# RGMII.net
KiCad netlist of a schematic drawn in Altium Designer
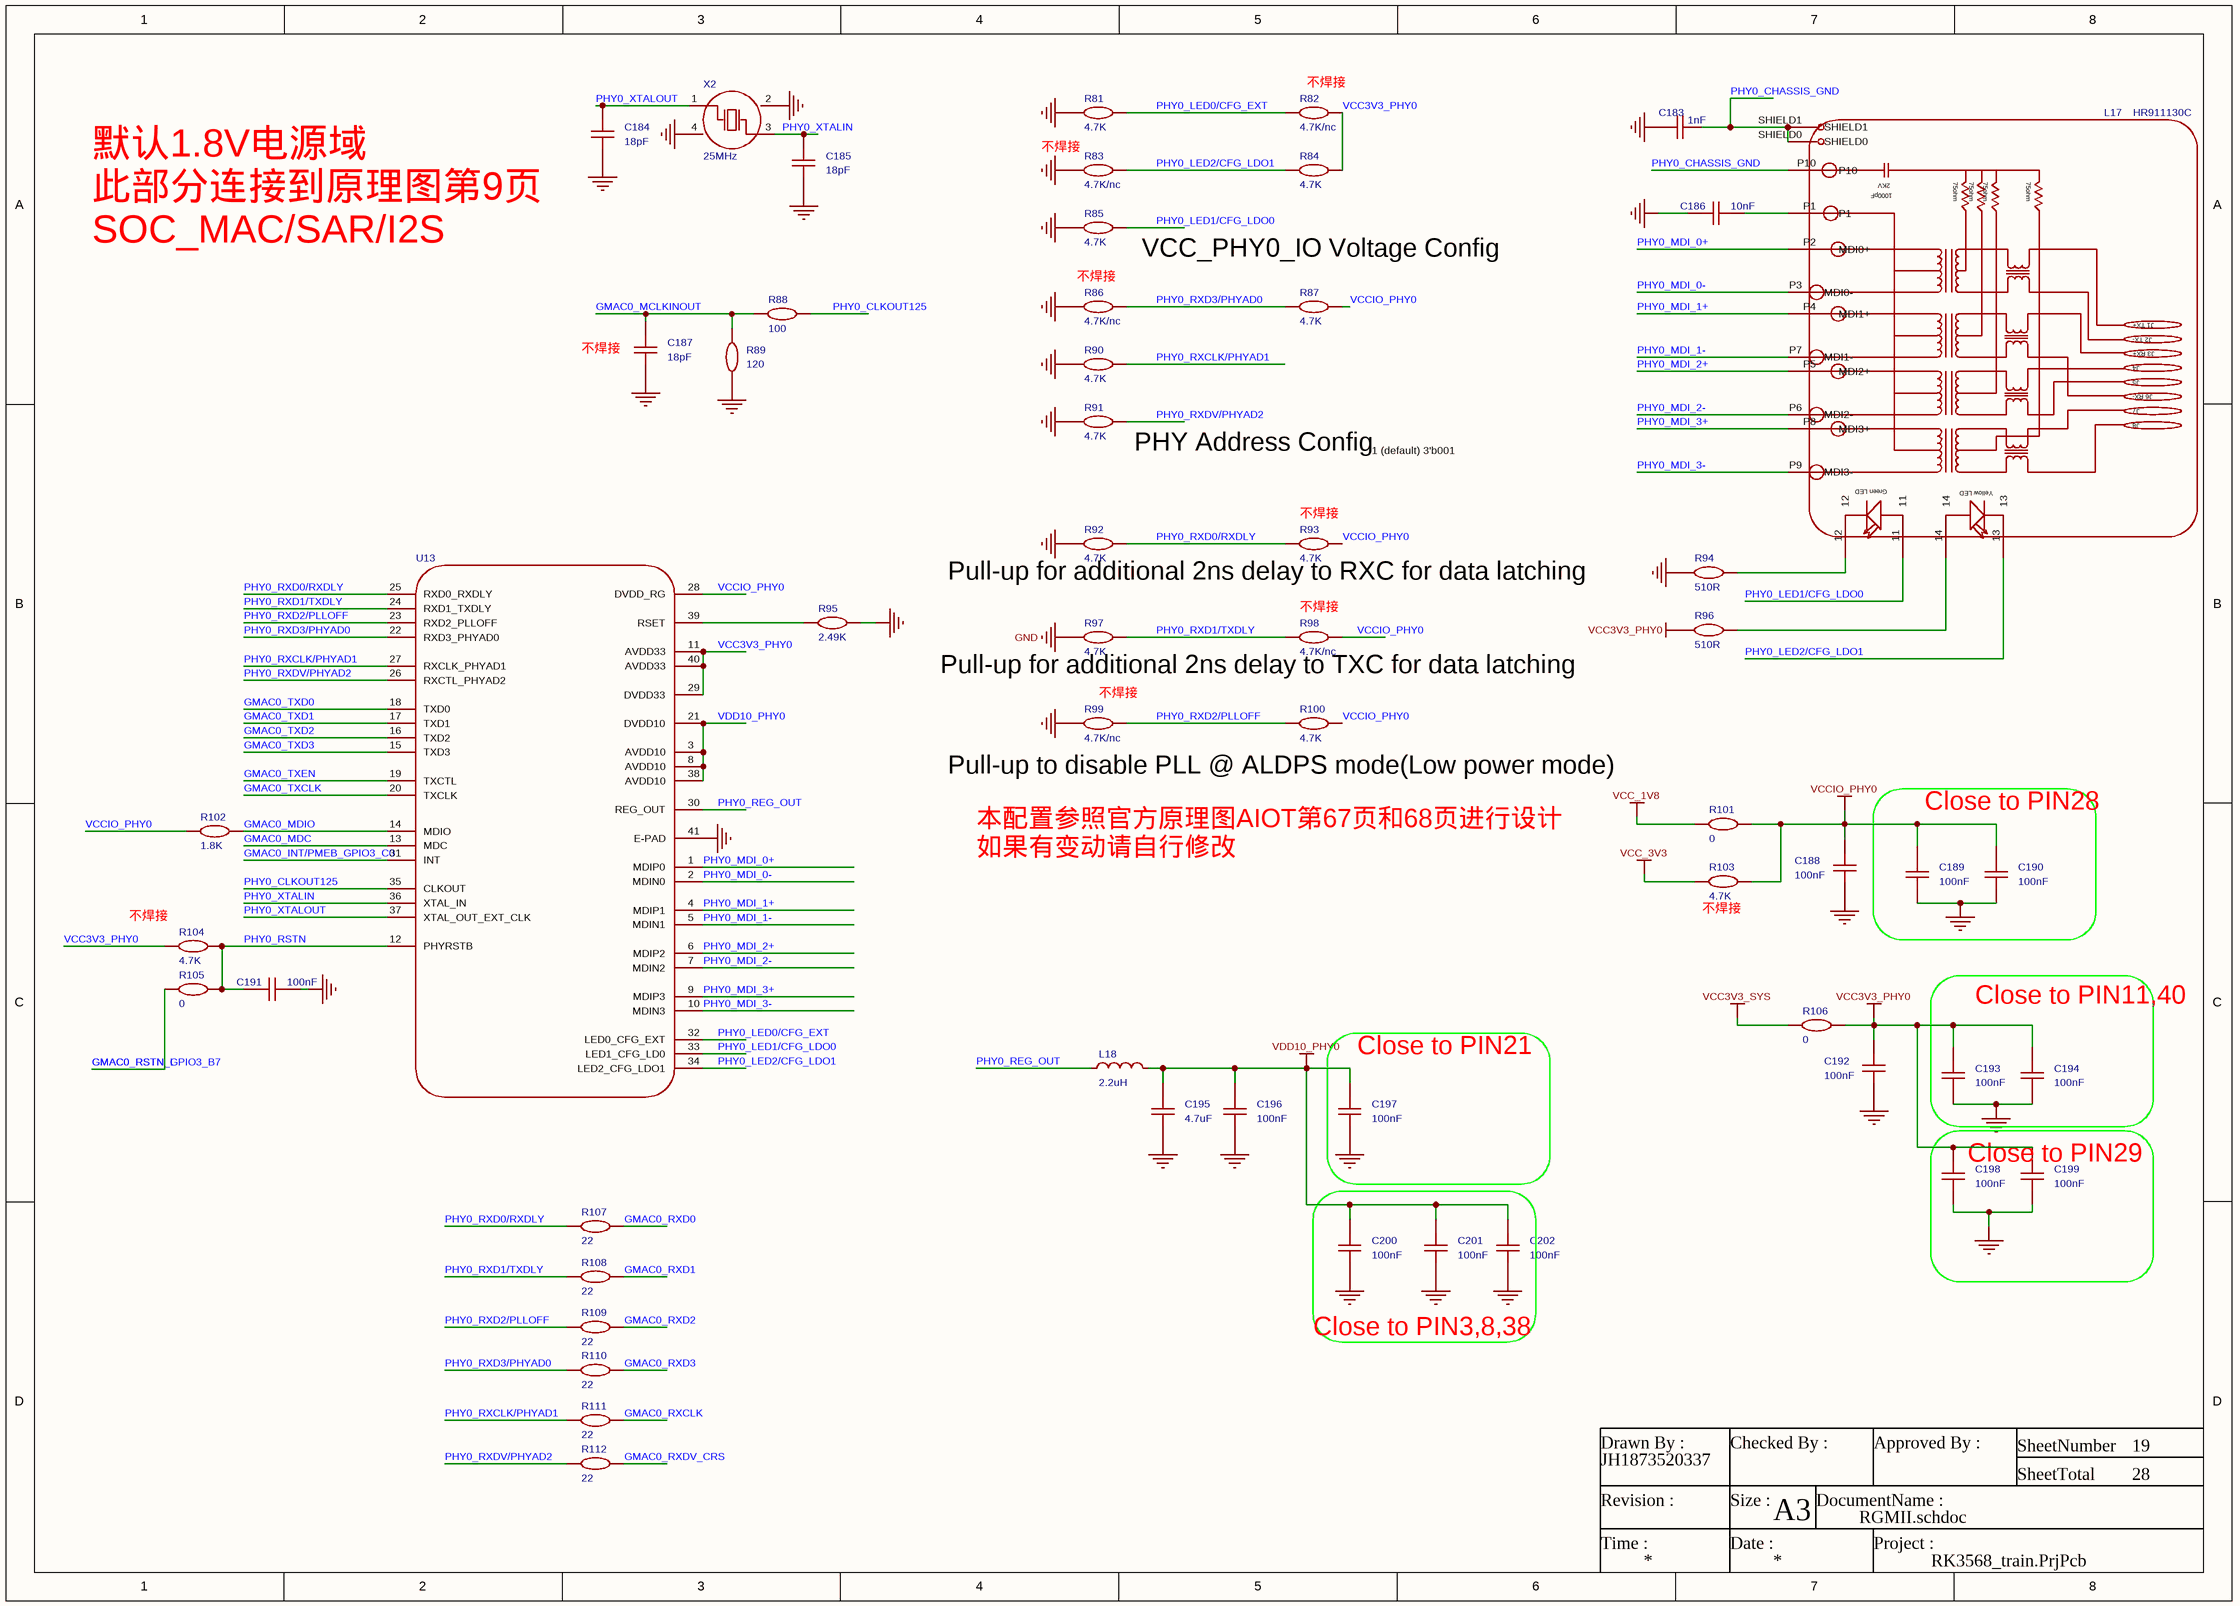
[diagram p0: RGMII.schdoc]

(export (version "E")
  (design (tool "Eeschema 10.0.6"))
  (components
    (comp (ref "C183")
      (value "1nF")
      (footprint "C1206")
      (description "容值:1nF;精度:±10%;额定电压:2kV;温度系数:X7R;")
      (fields (field (name "MANUFACTURER") "FH(风华)") (field (name "MANUFACTURERPART") "1206B102K202NT"))
      (libsource (lib "altium-import") (part "root_0_1206B102K202NT_"))
    )
    (comp (ref "C184")
      (value "18pF")
      (footprint "MYC0402")
      (description "容值:1uF;精度:±10%;额定电压:50V;材质(温度系数):X5R;")
      (fields (field (name "MANUFACTURER") "SAMSUNG(三星)") (field (name "MANUFACTURERPART") "CL10A105KB8NNNC"))
      (libsource (lib "altium-import") (part "root_3_CL10A105KB8NNNC_"))
    )
    (comp (ref "C185")
      (value "18pF")
      (footprint "MYC0402")
      (description "容值:1uF;精度:±10%;额定电压:50V;材质(温度系数):X5R;")
      (fields (field (name "MANUFACTURER") "SAMSUNG(三星)") (field (name "MANUFACTURERPART") "CL10A105KB8NNNC"))
      (libsource (lib "altium-import") (part "root_3_CL10A105KB8NNNC_"))
    )
    (comp (ref "C186")
      (value "10nF")
      (footprint "MYC0402")
      (description "容值:1uF;精度:±10%;额定电压:50V;材质(温度系数):X5R;")
      (fields (field (name "MANUFACTURER") "SAMSUNG(三星)") (field (name "MANUFACTURERPART") "CL10A105KB8NNNC"))
      (libsource (lib "altium-import") (part "root_2_CL10A105KB8NNNC_"))
    )
    (comp (ref "C187")
      (value "18pF")
      (footprint "MYC0402")
      (description "容值:1uF;精度:±10%;额定电压:50V;材质(温度系数):X5R;")
      (fields (field (name "MANUFACTURER") "SAMSUNG(三星)") (field (name "MANUFACTURERPART") "CL10A105KB8NNNC"))
      (libsource (lib "altium-import") (part "root_3_CL10A105KB8NNNC_"))
    )
    (comp (ref "C188")
      (value "100nF")
      (footprint "C0603")
      (libsource (lib "altium-import") (part "root_1_CAP_0603_"))
    )
    (comp (ref "C189")
      (value "100nF")
      (footprint "MYC0402")
      (description "容值:1uF;精度:±10%;额定电压:50V;材质(温度系数):X5R;")
      (fields (field (name "MANUFACTURER") "SAMSUNG(三星)") (field (name "MANUFACTURERPART") "CL10A105KB8NNNC"))
      (libsource (lib "altium-import") (part "root_3_CL10A105KB8NNNC_"))
    )
    (comp (ref "C190")
      (value "100nF")
      (footprint "MYC0402")
      (description "容值:1uF;精度:±10%;额定电压:50V;材质(温度系数):X5R;")
      (fields (field (name "MANUFACTURER") "SAMSUNG(三星)") (field (name "MANUFACTURERPART") "CL10A105KB8NNNC"))
      (libsource (lib "altium-import") (part "root_3_CL10A105KB8NNNC_"))
    )
    (comp (ref "C191")
      (value "100nF")
      (footprint "MYC0402")
      (description "容值:1uF;精度:±10%;额定电压:50V;材质(温度系数):X5R;")
      (fields (field (name "MANUFACTURER") "SAMSUNG(三星)") (field (name "MANUFACTURERPART") "CL10A105KB8NNNC"))
      (libsource (lib "altium-import") (part "root_2_CL10A105KB8NNNC_"))
    )
    (comp (ref "C192")
      (value "100nF")
      (footprint "C0603")
      (libsource (lib "altium-import") (part "root_1_CAP_0603_"))
    )
    (comp (ref "C193")
      (value "100nF")
      (footprint "MYC0402")
      (description "容值:1uF;精度:±10%;额定电压:50V;材质(温度系数):X5R;")
      (fields (field (name "MANUFACTURER") "SAMSUNG(三星)") (field (name "MANUFACTURERPART") "CL10A105KB8NNNC"))
      (libsource (lib "altium-import") (part "root_3_CL10A105KB8NNNC_"))
    )
    (comp (ref "C194")
      (value "100nF")
      (footprint "MYC0402")
      (description "容值:1uF;精度:±10%;额定电压:50V;材质(温度系数):X5R;")
      (fields (field (name "MANUFACTURER") "SAMSUNG(三星)") (field (name "MANUFACTURERPART") "CL10A105KB8NNNC"))
      (libsource (lib "altium-import") (part "root_3_CL10A105KB8NNNC_"))
    )
    (comp (ref "C195")
      (value "4.7uF")
      (footprint "C0603")
      (libsource (lib "altium-import") (part "root_1_CAP_0603_"))
    )
    (comp (ref "C196")
      (value "100nF")
      (footprint "MYC0402")
      (description "容值:1uF;精度:±10%;额定电压:50V;材质(温度系数):X5R;")
      (fields (field (name "MANUFACTURER") "SAMSUNG(三星)") (field (name "MANUFACTURERPART") "CL10A105KB8NNNC"))
      (libsource (lib "altium-import") (part "root_3_CL10A105KB8NNNC_"))
    )
    (comp (ref "C197")
      (value "100nF")
      (footprint "MYC0402")
      (description "容值:1uF;精度:±10%;额定电压:50V;材质(温度系数):X5R;")
      (fields (field (name "MANUFACTURER") "SAMSUNG(三星)") (field (name "MANUFACTURERPART") "CL10A105KB8NNNC"))
      (libsource (lib "altium-import") (part "root_3_CL10A105KB8NNNC_"))
    )
    (comp (ref "C198")
      (value "100nF")
      (footprint "C0603")
      (libsource (lib "altium-import") (part "root_1_CAP_0603_"))
    )
    (comp (ref "C199")
      (value "100nF")
      (footprint "MYC0402")
      (description "容值:1uF;精度:±10%;额定电压:50V;材质(温度系数):X5R;")
      (fields (field (name "MANUFACTURER") "SAMSUNG(三星)") (field (name "MANUFACTURERPART") "CL10A105KB8NNNC"))
      (libsource (lib "altium-import") (part "root_3_CL10A105KB8NNNC_"))
    )
    (comp (ref "C200")
      (value "100nF")
      (footprint "MYC0402")
      (description "容值:1uF;精度:±10%;额定电压:50V;材质(温度系数):X5R;")
      (fields (field (name "MANUFACTURER") "SAMSUNG(三星)") (field (name "MANUFACTURERPART") "CL10A105KB8NNNC"))
      (libsource (lib "altium-import") (part "root_3_CL10A105KB8NNNC_"))
    )
    (comp (ref "C201")
      (value "100nF")
      (footprint "MYC0402")
      (description "容值:1uF;精度:±10%;额定电压:50V;材质(温度系数):X5R;")
      (fields (field (name "MANUFACTURER") "SAMSUNG(三星)") (field (name "MANUFACTURERPART") "CL10A105KB8NNNC"))
      (libsource (lib "altium-import") (part "root_3_CL10A105KB8NNNC_"))
    )
    (comp (ref "C202")
      (value "100nF")
      (footprint "MYC0402")
      (description "容值:1uF;精度:±10%;额定电压:50V;材质(温度系数):X5R;")
      (fields (field (name "MANUFACTURER") "SAMSUNG(三星)") (field (name "MANUFACTURERPART") "CL10A105KB8NNNC"))
      (libsource (lib "altium-import") (part "root_3_CL10A105KB8NNNC_"))
    )
    (comp (ref "L17")
      (value "HR911130C")
      (footprint "RJ45-TH_HR911130C")
      (description "连接器类型:RJ45插座;端口数量:1;安装方式:弯插;屏蔽:有屏蔽;LED:带LED;等级:-;工作温度范围:-;")
      (fields (field (name "MANUFACTURER") "HANRUN(汉仁)"))
      (libsource (lib "altium-import") (part "root_2_mirrored_HR911130C_"))
    )
    (comp (ref "L18")
      (value "2.2uH")
      (footprint "IND-SMD_L2.5-W2.0_MHCHL2520")
      (description "电感值:2.2uH;精度:±20%;额定电流:3A;饱和电流(Isat):3.8A;类型:一体成型电感;")
      (fields
        (field (name "MANUFACTURER") "cjiang(长江微电)")
        (field (name "MANUFACTURERPART") "FTC252012S2R2MBCA")
      )
      (libsource (lib "altium-import") (part "root_0_FTC252012S2R2MBCA_"))
    )
    (comp (ref "R81")
      (value "4.7K")
      (footprint "R0402")
      (libsource (lib "altium-import") (part "root_0_Res_0402_"))
    )
    (comp (ref "R82")
      (value "4.7K/nc")
      (footprint "R0402")
      (libsource (lib "altium-import") (part "root_0_Res_0402_"))
    )
    (comp (ref "R83")
      (value "4.7K/nc")
      (footprint "R0402")
      (libsource (lib "altium-import") (part "root_0_Res_0402_"))
    )
    (comp (ref "R84")
      (value "4.7K")
      (footprint "R0402")
      (libsource (lib "altium-import") (part "root_0_Res_0402_"))
    )
    (comp (ref "R85")
      (value "4.7K")
      (footprint "R0402")
      (libsource (lib "altium-import") (part "root_0_Res_0402_"))
    )
    (comp (ref "R86")
      (value "4.7K/nc")
      (footprint "R0402")
      (libsource (lib "altium-import") (part "root_0_Res_0402_"))
    )
    (comp (ref "R87")
      (value "4.7K")
      (footprint "R0402")
      (libsource (lib "altium-import") (part "root_0_Res_0402_"))
    )
    (comp (ref "R88")
      (value "100")
      (footprint "R0402")
      (libsource (lib "altium-import") (part "root_0_Res_0402_"))
    )
    (comp (ref "R89")
      (value "120")
      (footprint "R0402")
      (libsource (lib "altium-import") (part "root_1_Res_0402_"))
    )
    (comp (ref "R90")
      (value "4.7K")
      (footprint "R0402")
      (libsource (lib "altium-import") (part "root_0_Res_0402_"))
    )
    (comp (ref "R91")
      (value "4.7K")
      (footprint "R0402")
      (libsource (lib "altium-import") (part "root_0_Res_0402_"))
    )
    (comp (ref "R92")
      (value "4.7K")
      (footprint "R0402")
      (libsource (lib "altium-import") (part "root_0_Res_0402_"))
    )
    (comp (ref "R93")
      (value "4.7K")
      (footprint "R0402")
      (libsource (lib "altium-import") (part "root_0_Res_0402_"))
    )
    (comp (ref "R94")
      (value "510R")
      (footprint "R0402")
      (libsource (lib "altium-import") (part "root_0_Res_0402_"))
    )
    (comp (ref "R95")
      (value "2.49K")
      (footprint "R0402")
      (libsource (lib "altium-import") (part "root_0_Res_0402_"))
    )
    (comp (ref "R96")
      (value "510R")
      (footprint "R0402")
      (libsource (lib "altium-import") (part "root_0_Res_0402_"))
    )
    (comp (ref "R97")
      (value "4.7K")
      (footprint "R0402")
      (libsource (lib "altium-import") (part "root_0_Res_0402_"))
    )
    (comp (ref "R98")
      (value "4.7K/nc")
      (footprint "R0402")
      (libsource (lib "altium-import") (part "root_0_Res_0402_"))
    )
    (comp (ref "R99")
      (value "4.7K/nc")
      (footprint "R0402")
      (libsource (lib "altium-import") (part "root_0_Res_0402_"))
    )
    (comp (ref "R100")
      (value "4.7K")
      (footprint "R0402")
      (libsource (lib "altium-import") (part "root_0_Res_0402_"))
    )
    (comp (ref "R101")
      (value "0")
      (footprint "R0603")
      (libsource (lib "altium-import") (part "root_0_Res_0603_"))
    )
    (comp (ref "R102")
      (value "1.8K")
      (footprint "R0402")
      (libsource (lib "altium-import") (part "root_0_Res_0402_"))
    )
    (comp (ref "R103")
      (value "4.7K")
      (footprint "R0402")
      (libsource (lib "altium-import") (part "root_0_Res_0402_"))
    )
    (comp (ref "R104")
      (value "4.7K")
      (footprint "R0402")
      (libsource (lib "altium-import") (part "root_0_Res_0402_"))
    )
    (comp (ref "R105")
      (value "0")
      (footprint "R0402")
      (libsource (lib "altium-import") (part "root_0_Res_0402_"))
    )
    (comp (ref "R106")
      (value "0")
      (footprint "R0603")
      (libsource (lib "altium-import") (part "root_0_Res_0603_"))
    )
    (comp (ref "R107")
      (value "22")
      (footprint "R0402")
      (libsource (lib "altium-import") (part "root_0_Res_0402_"))
    )
    (comp (ref "R108")
      (value "22")
      (footprint "R0402")
      (libsource (lib "altium-import") (part "root_0_Res_0402_"))
    )
    (comp (ref "R109")
      (value "22")
      (footprint "R0402")
      (libsource (lib "altium-import") (part "root_0_Res_0402_"))
    )
    (comp (ref "R110")
      (value "22")
      (footprint "R0402")
      (libsource (lib "altium-import") (part "root_0_Res_0402_"))
    )
    (comp (ref "R111")
      (value "22")
      (footprint "R0402")
      (libsource (lib "altium-import") (part "root_0_Res_0402_"))
    )
    (comp (ref "R112")
      (value "22")
      (footprint "R0402")
      (libsource (lib "altium-import") (part "root_0_Res_0402_"))
    )
    (comp (ref "U13")
      (value "~")
      (footprint "RTL8211F-CG")
      (libsource (lib "altium-import") (part "root_0_RTL8211F-CG_"))
    )
    (comp (ref "X2")
      (value "25MHz")
      (footprint "CRYSTAL-SMD_4P-L3.2-W2.5-BL")
      (description "晶振类型:贴片晶振;频率:25MHz;常温频差:±10ppm;负载电容:12pF;频率稳定度:±20ppm;")
      (fields (field (name "MANUFACTURER") "YXC(扬兴晶振)") (field (name "MANUFACTURERPART") "X322525MOB4SI"))
      (libsource (lib "altium-import") (part "root_2_mirrored_X322525MOB4SI_"))
    )
  )
  (nets
    (net (code "1") (name "/GMAC0_INT{slash}PMEB_GPIO3_C0") (class "Default")
      (node (ref "U13") (pin "31") (pinfunction "INT_31") (pintype "passive"))
    )
    (net (code "2") (name "/GMAC0_MCLKINOUT") (class "Default")
      (node (ref "C187") (pin "1") (pinfunction "1_1") (pintype "passive"))
      (node (ref "R88") (pin "1") (pinfunction "1_1") (pintype "passive"))
      (node (ref "R89") (pin "2") (pinfunction "2_2") (pintype "passive"))
    )
    (net (code "3") (name "/GMAC0_MDC") (class "Default")
      (node (ref "U13") (pin "13") (pinfunction "MDC_13") (pintype "passive"))
    )
    (net (code "4") (name "/GMAC0_MDIO") (class "Default")
      (node (ref "R102") (pin "2") (pinfunction "2_2") (pintype "passive"))
      (node (ref "U13") (pin "14") (pinfunction "MDIO_14") (pintype "passive"))
    )
    (net (code "5") (name "/GMAC0_RSTN_GPIO3_B7") (class "Default")
      (node (ref "R105") (pin "1") (pinfunction "1_1") (pintype "passive"))
    )
    (net (code "6") (name "/GMAC0_RXCLK") (class "Default")
      (node (ref "R111") (pin "2") (pinfunction "2_2") (pintype "passive"))
    )
    (net (code "7") (name "/GMAC0_RXD0") (class "Default")
      (node (ref "R107") (pin "2") (pinfunction "2_2") (pintype "passive"))
    )
    (net (code "8") (name "/GMAC0_RXD1") (class "Default")
      (node (ref "R108") (pin "2") (pinfunction "2_2") (pintype "passive"))
    )
    (net (code "9") (name "/GMAC0_RXD2") (class "Default")
      (node (ref "R109") (pin "2") (pinfunction "2_2") (pintype "passive"))
    )
    (net (code "10") (name "/GMAC0_RXD3") (class "Default")
      (node (ref "R110") (pin "2") (pinfunction "2_2") (pintype "passive"))
    )
    (net (code "11") (name "/GMAC0_RXDV_CRS") (class "Default")
      (node (ref "R112") (pin "2") (pinfunction "2_2") (pintype "passive"))
    )
    (net (code "12") (name "/GMAC0_TXCLK") (class "Default")
      (node (ref "U13") (pin "20") (pinfunction "TXCLK_20") (pintype "passive"))
    )
    (net (code "13") (name "/GMAC0_TXD0") (class "Default")
      (node (ref "U13") (pin "18") (pinfunction "TXD0_18") (pintype "passive"))
    )
    (net (code "14") (name "/GMAC0_TXD1") (class "Default")
      (node (ref "U13") (pin "17") (pinfunction "TXD1_17") (pintype "passive"))
    )
    (net (code "15") (name "/GMAC0_TXD2") (class "Default")
      (node (ref "U13") (pin "16") (pinfunction "TXD2_16") (pintype "passive"))
    )
    (net (code "16") (name "/GMAC0_TXD3") (class "Default")
      (node (ref "U13") (pin "15") (pinfunction "TXD3_15") (pintype "passive"))
    )
    (net (code "17") (name "/GMAC0_TXEN") (class "Default")
      (node (ref "U13") (pin "19") (pinfunction "TXCTL_19") (pintype "passive"))
    )
    (net (code "18") (name "/PHY0_CHASSIS_GND") (class "Default")
      (node (ref "C183") (pin "2") (pinfunction "2_2") (pintype "passive"))
      (node (ref "L17") (pin "P10") (pinfunction "P10_P10") (pintype "passive"))
      (node (ref "L17") (pin "SHIELD0") (pinfunction "SHIELD0_SHIELD0") (pintype "passive"))
      (node (ref "L17") (pin "SHIELD1") (pinfunction "SHIELD1_SHIELD1") (pintype "passive"))
    )
    (net (code "19") (name "/PHY0_CLKOUT125") (class "Default")
      (node (ref "R88") (pin "2") (pinfunction "2_2") (pintype "passive"))
      (node (ref "U13") (pin "35") (pinfunction "CLKOUT_35") (pintype "passive"))
    )
    (net (code "20") (name "/PHY0_LED0{slash}CFG_EXT") (class "Default")
      (node (ref "R81") (pin "2") (pinfunction "2_2") (pintype "passive"))
      (node (ref "R82") (pin "1") (pinfunction "1_1") (pintype "passive"))
      (node (ref "U13") (pin "32") (pinfunction "LED0_CFG_EXT_32") (pintype "passive"))
    )
    (net (code "21") (name "/PHY0_LED1{slash}CFG_LDO0") (class "Default")
      (node (ref "L17") (pin "11") (pinfunction "11_11") (pintype "passive"))
      (node (ref "R85") (pin "2") (pinfunction "2_2") (pintype "passive"))
      (node (ref "U13") (pin "33") (pinfunction "LED1_CFG_LD0_33") (pintype "passive"))
    )
    (net (code "22") (name "/PHY0_LED2{slash}CFG_LDO1") (class "Default")
      (node (ref "L17") (pin "13") (pinfunction "13_13") (pintype "passive"))
      (node (ref "R83") (pin "2") (pinfunction "2_2") (pintype "passive"))
      (node (ref "R84") (pin "1") (pinfunction "1_1") (pintype "passive"))
      (node (ref "U13") (pin "34") (pinfunction "LED2_CFG_LDO1_34") (pintype "passive"))
    )
    (net (code "23") (name "/PHY0_MDI_0+") (class "Default")
      (node (ref "L17") (pin "P2") (pinfunction "MDI0+_P2") (pintype "passive"))
      (node (ref "U13") (pin "1") (pinfunction "MDIP0_1") (pintype "passive"))
    )
    (net (code "24") (name "/PHY0_MDI_0-") (class "Default")
      (node (ref "L17") (pin "P3") (pinfunction "MDI0-_P3") (pintype "passive"))
      (node (ref "U13") (pin "2") (pinfunction "MDIN0_2") (pintype "passive"))
    )
    (net (code "25") (name "/PHY0_MDI_1+") (class "Default")
      (node (ref "L17") (pin "P4") (pinfunction "MDI1+_P4") (pintype "passive"))
      (node (ref "U13") (pin "4") (pinfunction "MDIP1_4") (pintype "passive"))
    )
    (net (code "26") (name "/PHY0_MDI_1-") (class "Default")
      (node (ref "L17") (pin "P7") (pinfunction "MDI1-_P7") (pintype "passive"))
      (node (ref "U13") (pin "5") (pinfunction "MDIN1_5") (pintype "passive"))
    )
    (net (code "27") (name "/PHY0_MDI_2+") (class "Default")
      (node (ref "L17") (pin "P5") (pinfunction "MDI2+_P5") (pintype "passive"))
      (node (ref "U13") (pin "6") (pinfunction "MDIP2_6") (pintype "passive"))
    )
    (net (code "28") (name "/PHY0_MDI_2-") (class "Default")
      (node (ref "L17") (pin "P6") (pinfunction "MDI2-_P6") (pintype "passive"))
      (node (ref "U13") (pin "7") (pinfunction "MDIN2_7") (pintype "passive"))
    )
    (net (code "29") (name "/PHY0_MDI_3+") (class "Default")
      (node (ref "L17") (pin "P8") (pinfunction "MDI3+_P8") (pintype "passive"))
      (node (ref "U13") (pin "9") (pinfunction "MDIP3_9") (pintype "passive"))
    )
    (net (code "30") (name "/PHY0_MDI_3-") (class "Default")
      (node (ref "L17") (pin "P9") (pinfunction "MDI3-_P9") (pintype "passive"))
      (node (ref "U13") (pin "10") (pinfunction "MDIN3_10") (pintype "passive"))
    )
    (net (code "31") (name "/PHY0_REG_OUT") (class "Default")
      (node (ref "L18") (pin "1") (pinfunction "1_1") (pintype "passive"))
      (node (ref "U13") (pin "30") (pinfunction "REG_OUT_30") (pintype "passive"))
    )
    (net (code "32") (name "/PHY0_RSTN") (class "Default")
      (node (ref "C191") (pin "2") (pinfunction "2_2") (pintype "passive"))
      (node (ref "R104") (pin "2") (pinfunction "2_2") (pintype "passive"))
      (node (ref "R105") (pin "2") (pinfunction "2_2") (pintype "passive"))
      (node (ref "U13") (pin "12") (pinfunction "PHYRSTB_12") (pintype "passive"))
    )
    (net (code "33") (name "/PHY0_RXCLK{slash}PHYAD1") (class "Default")
      (node (ref "R111") (pin "1") (pinfunction "1_1") (pintype "passive"))
      (node (ref "R90") (pin "2") (pinfunction "2_2") (pintype "passive"))
      (node (ref "U13") (pin "27") (pinfunction "RXCLK_PHYAD1_27") (pintype "passive"))
    )
    (net (code "34") (name "/PHY0_RXD0{slash}RXDLY") (class "Default")
      (node (ref "R107") (pin "1") (pinfunction "1_1") (pintype "passive"))
      (node (ref "R92") (pin "2") (pinfunction "2_2") (pintype "passive"))
      (node (ref "R93") (pin "1") (pinfunction "1_1") (pintype "passive"))
      (node (ref "U13") (pin "25") (pinfunction "RXD0_RXDLY_25") (pintype "passive"))
    )
    (net (code "35") (name "/PHY0_RXD1{slash}TXDLY") (class "Default")
      (node (ref "R108") (pin "1") (pinfunction "1_1") (pintype "passive"))
      (node (ref "R97") (pin "2") (pinfunction "2_2") (pintype "passive"))
      (node (ref "R98") (pin "1") (pinfunction "1_1") (pintype "passive"))
      (node (ref "U13") (pin "24") (pinfunction "RXD1_TXDLY_24") (pintype "passive"))
    )
    (net (code "36") (name "/PHY0_RXD2{slash}PLLOFF") (class "Default")
      (node (ref "R100") (pin "1") (pinfunction "1_1") (pintype "passive"))
      (node (ref "R109") (pin "1") (pinfunction "1_1") (pintype "passive"))
      (node (ref "R99") (pin "2") (pinfunction "2_2") (pintype "passive"))
      (node (ref "U13") (pin "23") (pinfunction "RXD2_PLLOFF_23") (pintype "passive"))
    )
    (net (code "37") (name "/PHY0_RXD3{slash}PHYAD0") (class "Default")
      (node (ref "R110") (pin "1") (pinfunction "1_1") (pintype "passive"))
      (node (ref "R86") (pin "2") (pinfunction "2_2") (pintype "passive"))
      (node (ref "R87") (pin "1") (pinfunction "1_1") (pintype "passive"))
      (node (ref "U13") (pin "22") (pinfunction "RXD3_PHYAD0_22") (pintype "passive"))
    )
    (net (code "38") (name "/PHY0_RXDV{slash}PHYAD2") (class "Default")
      (node (ref "R112") (pin "1") (pinfunction "1_1") (pintype "passive"))
      (node (ref "R91") (pin "2") (pinfunction "2_2") (pintype "passive"))
      (node (ref "U13") (pin "26") (pinfunction "RXCTL_PHYAD2_26") (pintype "passive"))
    )
    (net (code "39") (name "/PHY0_XTALIN") (class "Default")
      (node (ref "C185") (pin "1") (pinfunction "1_1") (pintype "passive"))
      (node (ref "U13") (pin "36") (pinfunction "XTAL_IN_36") (pintype "passive"))
      (node (ref "X2") (pin "3") (pinfunction "OSC2_3") (pintype "passive"))
    )
    (net (code "40") (name "/PHY0_XTALOUT") (class "Default")
      (node (ref "C184") (pin "1") (pinfunction "1_1") (pintype "passive"))
      (node (ref "U13") (pin "37") (pinfunction "XTAL_OUT_EXT_CLK_37") (pintype "passive"))
      (node (ref "X2") (pin "1") (pinfunction "OSC1_1") (pintype "passive"))
    )
    (net (code "41") (name "GND") (class "Default")
      (node (ref "C183") (pin "1") (pinfunction "1_1") (pintype "passive"))
      (node (ref "C184") (pin "2") (pinfunction "2_2") (pintype "passive"))
      (node (ref "C185") (pin "2") (pinfunction "2_2") (pintype "passive"))
      (node (ref "C186") (pin "2") (pinfunction "2_2") (pintype "passive"))
      (node (ref "C187") (pin "2") (pinfunction "2_2") (pintype "passive"))
      (node (ref "C188") (pin "1") (pinfunction "1_1") (pintype "passive"))
      (node (ref "C189") (pin "2") (pinfunction "2_2") (pintype "passive"))
      (node (ref "C190") (pin "2") (pinfunction "2_2") (pintype "passive"))
      (node (ref "C191") (pin "1") (pinfunction "1_1") (pintype "passive"))
      (node (ref "C192") (pin "1") (pinfunction "1_1") (pintype "passive"))
      (node (ref "C193") (pin "2") (pinfunction "2_2") (pintype "passive"))
      (node (ref "C194") (pin "2") (pinfunction "2_2") (pintype "passive"))
      (node (ref "C195") (pin "1") (pinfunction "1_1") (pintype "passive"))
      (node (ref "C196") (pin "2") (pinfunction "2_2") (pintype "passive"))
      (node (ref "C197") (pin "2") (pinfunction "2_2") (pintype "passive"))
      (node (ref "C198") (pin "1") (pinfunction "1_1") (pintype "passive"))
      (node (ref "C199") (pin "2") (pinfunction "2_2") (pintype "passive"))
      (node (ref "C200") (pin "2") (pinfunction "2_2") (pintype "passive"))
      (node (ref "C201") (pin "2") (pinfunction "2_2") (pintype "passive"))
      (node (ref "C202") (pin "2") (pinfunction "2_2") (pintype "passive"))
      (node (ref "R81") (pin "1") (pinfunction "1_1") (pintype "passive"))
      (node (ref "R83") (pin "1") (pinfunction "1_1") (pintype "passive"))
      (node (ref "R85") (pin "1") (pinfunction "1_1") (pintype "passive"))
      (node (ref "R86") (pin "1") (pinfunction "1_1") (pintype "passive"))
      (node (ref "R89") (pin "1") (pinfunction "1_1") (pintype "passive"))
      (node (ref "R90") (pin "1") (pinfunction "1_1") (pintype "passive"))
      (node (ref "R91") (pin "1") (pinfunction "1_1") (pintype "passive"))
      (node (ref "R92") (pin "1") (pinfunction "1_1") (pintype "passive"))
      (node (ref "R94") (pin "1") (pinfunction "1_1") (pintype "passive"))
      (node (ref "R95") (pin "2") (pinfunction "2_2") (pintype "passive"))
      (node (ref "R97") (pin "1") (pinfunction "1_1") (pintype "passive"))
      (node (ref "R99") (pin "1") (pinfunction "1_1") (pintype "passive"))
      (node (ref "U13") (pin "41") (pinfunction "E-PAD_41") (pintype "passive"))
      (node (ref "X2") (pin "2") (pinfunction "GND_2") (pintype "passive"))
      (node (ref "X2") (pin "4") (pinfunction "GND_4") (pintype "passive"))
    )
    (net (code "42") (name "Net-(C186-Pad1)") (class "Default")
      (node (ref "C186") (pin "1") (pinfunction "1_1") (pintype "passive"))
      (node (ref "L17") (pin "P1") (pinfunction "P1_P1") (pintype "passive"))
    )
    (net (code "43") (name "Net-(L17-Pad12)") (class "Default")
      (node (ref "L17") (pin "12") (pinfunction "12_12") (pintype "passive"))
      (node (ref "R94") (pin "2") (pinfunction "2_2") (pintype "passive"))
    )
    (net (code "44") (name "Net-(L17-Pad14)") (class "Default")
      (node (ref "L17") (pin "14") (pinfunction "14_14") (pintype "passive"))
      (node (ref "R96") (pin "2") (pinfunction "2_2") (pintype "passive"))
    )
    (net (code "45") (name "Net-(U13-RSET)") (class "Default")
      (node (ref "R95") (pin "1") (pinfunction "1_1") (pintype "passive"))
      (node (ref "U13") (pin "39") (pinfunction "RSET_39") (pintype "passive"))
    )
    (net (code "46") (name "VCC3V3_PHY0") (class "Default")
      (node (ref "C192") (pin "2") (pinfunction "2_2") (pintype "passive"))
      (node (ref "C193") (pin "1") (pinfunction "1_1") (pintype "passive"))
      (node (ref "C194") (pin "1") (pinfunction "1_1") (pintype "passive"))
      (node (ref "C198") (pin "2") (pinfunction "2_2") (pintype "passive"))
      (node (ref "C199") (pin "1") (pinfunction "1_1") (pintype "passive"))
      (node (ref "R104") (pin "1") (pinfunction "1_1") (pintype "passive"))
      (node (ref "R106") (pin "2") (pinfunction "2_2") (pintype "passive"))
      (node (ref "R82") (pin "2") (pinfunction "2_2") (pintype "passive"))
      (node (ref "R84") (pin "2") (pinfunction "2_2") (pintype "passive"))
      (node (ref "R96") (pin "1") (pinfunction "1_1") (pintype "passive"))
      (node (ref "U13") (pin "11") (pinfunction "AVDD33_11") (pintype "passive"))
      (node (ref "U13") (pin "29") (pinfunction "DVDD33_29") (pintype "passive"))
      (node (ref "U13") (pin "40") (pinfunction "AVDD33_40") (pintype "passive"))
    )
    (net (code "47") (name "VCC3V3_SYS") (class "Default")
      (node (ref "R106") (pin "1") (pinfunction "1_1") (pintype "passive"))
    )
    (net (code "48") (name "VCCIO_PHY0") (class "Default")
      (node (ref "C188") (pin "2") (pinfunction "2_2") (pintype "passive"))
      (node (ref "C189") (pin "1") (pinfunction "1_1") (pintype "passive"))
      (node (ref "C190") (pin "1") (pinfunction "1_1") (pintype "passive"))
      (node (ref "R100") (pin "2") (pinfunction "2_2") (pintype "passive"))
      (node (ref "R101") (pin "2") (pinfunction "2_2") (pintype "passive"))
      (node (ref "R102") (pin "1") (pinfunction "1_1") (pintype "passive"))
      (node (ref "R103") (pin "2") (pinfunction "2_2") (pintype "passive"))
      (node (ref "R87") (pin "2") (pinfunction "2_2") (pintype "passive"))
      (node (ref "R93") (pin "2") (pinfunction "2_2") (pintype "passive"))
      (node (ref "R98") (pin "2") (pinfunction "2_2") (pintype "passive"))
      (node (ref "U13") (pin "28") (pinfunction "DVDD_RG_28") (pintype "passive"))
    )
    (net (code "49") (name "VCC_1V8") (class "Default")
      (node (ref "R101") (pin "1") (pinfunction "1_1") (pintype "passive"))
    )
    (net (code "50") (name "VCC_3V3") (class "Default")
      (node (ref "R103") (pin "1") (pinfunction "1_1") (pintype "passive"))
    )
    (net (code "51") (name "VDD10_PHY0") (class "Default")
      (node (ref "C195") (pin "2") (pinfunction "2_2") (pintype "passive"))
      (node (ref "C196") (pin "1") (pinfunction "1_1") (pintype "passive"))
      (node (ref "C197") (pin "1") (pinfunction "1_1") (pintype "passive"))
      (node (ref "C200") (pin "1") (pinfunction "1_1") (pintype "passive"))
      (node (ref "C201") (pin "1") (pinfunction "1_1") (pintype "passive"))
      (node (ref "C202") (pin "1") (pinfunction "1_1") (pintype "passive"))
      (node (ref "L18") (pin "2") (pinfunction "2_2") (pintype "passive"))
      (node (ref "U13") (pin "21") (pinfunction "DVDD10_21") (pintype "passive"))
      (node (ref "U13") (pin "3") (pinfunction "AVDD10_3") (pintype "passive"))
      (node (ref "U13") (pin "38") (pinfunction "AVDD10_38") (pintype "passive"))
      (node (ref "U13") (pin "8") (pinfunction "AVDD10_8") (pintype "passive"))
    )
  )
)
